# 8.net
KiCad netlist of a schematic drawn in EAGLE
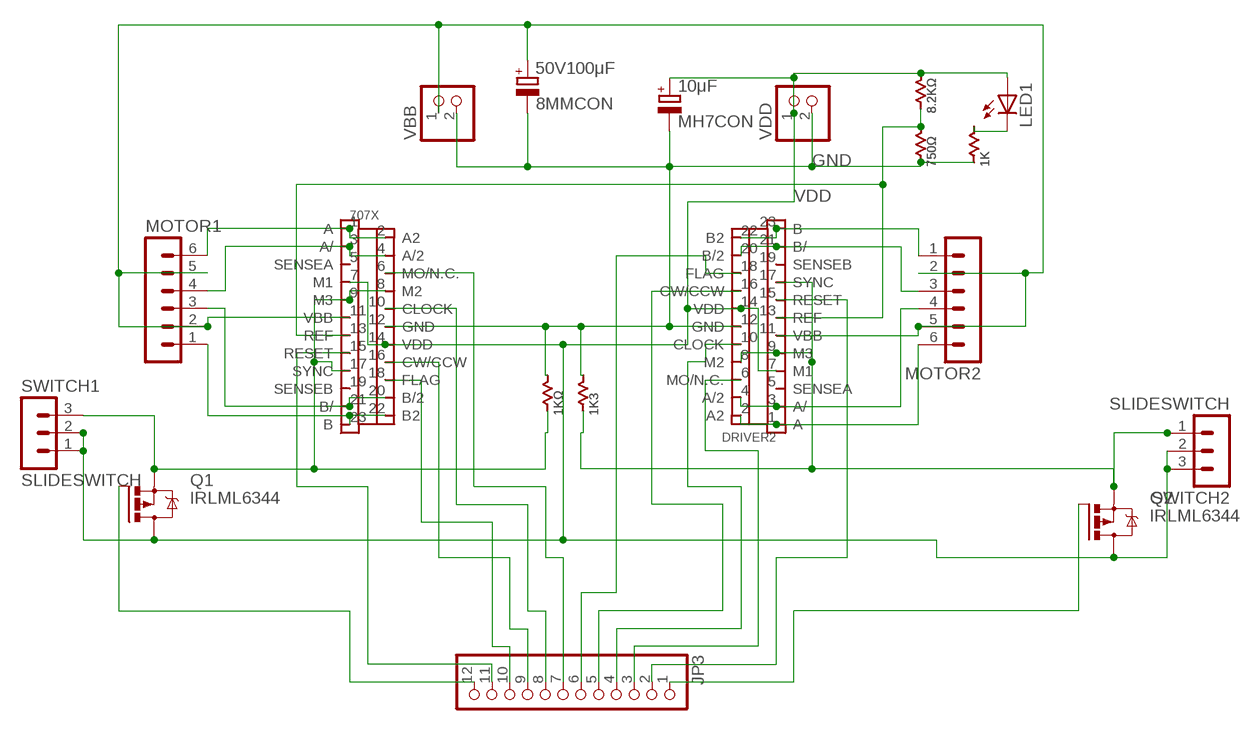
[diagram p0: schematic, sheet 1]

(export (version "E")
  (design (tool "Eeschema 10.0.6"))
  (components
    (comp (ref "1K")
      (value "R1608")
      (footprint "eagle-import:C1608")
      (libsource (lib "eagle-import") (part "R1608"))
    )
    (comp (ref "1K3")
      (value "R1608")
      (footprint "eagle-import:C1608")
      (libsource (lib "eagle-import") (part "R1608"))
    )
    (comp (ref "1KΩ")
      (value "R1608")
      (footprint "eagle-import:C1608")
      (libsource (lib "eagle-import") (part "R1608"))
    )
    (comp (ref "8.2KΩ")
      (value "1/6W")
      (footprint "eagle-import:1_6WRESISTANCE")
      (libsource (lib "eagle-import") (part "1/6W"))
    )
    (comp (ref "10μF")
      (value "MH7CON")
      (footprint "eagle-import:MH7CON")
      (libsource (lib "eagle-import") (part "MH7CON"))
    )
    (comp (ref "50V100μF")
      (value "8MMCON")
      (footprint "eagle-import:50V100FCON")
      (libsource (lib "eagle-import") (part "8MMCON"))
    )
    (comp (ref "707X")
      (value "SLA707X")
      (footprint "eagle-import:23-2PINHEAD")
      (libsource (lib "eagle-import") (part "SLA707X"))
    )
    (comp (ref "750Ω")
      (value "1/6W")
      (footprint "eagle-import:1_6WRESISTANCE")
      (libsource (lib "eagle-import") (part "1/6W"))
    )
    (comp (ref "DRIVER2")
      (value "SLA707X")
      (footprint "eagle-import:23-2PINHEAD")
      (libsource (lib "eagle-import") (part "SLA707X"))
    )
    (comp (ref "JP3")
      (value "PINHD-1X12")
      (footprint "eagle-import:1X12")
      (libsource (lib "eagle-import") (part "PINHD-1X12"))
    )
    (comp (ref "LED1")
      (value "OPTOCHIPLEDLED")
      (footprint "eagle-import:CHIP")
      (libsource (lib "eagle-import") (part "OPTOCHIPLEDLED"))
    )
    (comp (ref "MOTOR1")
      (value "MA06-1")
      (footprint "eagle-import:MA06-1")
      (libsource (lib "eagle-import") (part "MA06-1"))
    )
    (comp (ref "MOTOR2")
      (value "MA06-1")
      (footprint "eagle-import:MA06-1")
      (libsource (lib "eagle-import") (part "MA06-1"))
    )
    (comp (ref "Q1")
      (value "IRLML6344")
      (footprint "eagle-import:MICRO3")
      (libsource (lib "eagle-import") (part "IRLML5203"))
    )
    (comp (ref "Q2")
      (value "IRLML6344")
      (footprint "eagle-import:MICRO3")
      (libsource (lib "eagle-import") (part "IRLML5203"))
    )
    (comp (ref "SWITCH1")
      (value "SLIDESWITCH")
      (footprint "eagle-import:M251")
      (libsource (lib "eagle-import") (part "SLIDESWITCH"))
    )
    (comp (ref "SWITCH2")
      (value "SLIDESWITCH")
      (footprint "eagle-import:M251")
      (libsource (lib "eagle-import") (part "SLIDESWITCH"))
    )
    (comp (ref "VBB")
      (value "PINHD-1X2")
      (footprint "eagle-import:1X02")
      (libsource (lib "eagle-import") (part "PINHD-1X2"))
    )
    (comp (ref "VDD")
      (value "PINHD-1X2")
      (footprint "eagle-import:1X02")
      (libsource (lib "eagle-import") (part "PINHD-1X2"))
    )
  )
  (nets
    (net (code "1") (name "/GND") (class "Default")
      (node (ref "10μF") (pin "P$2") (pinfunction "-_P$2") (pintype "passive"))
      (node (ref "1K") (pin "2") (pinfunction "A_2") (pintype "bidirectional"))
      (node (ref "1K3") (pin "1") (pinfunction "B_1") (pintype "bidirectional"))
      (node (ref "1KΩ") (pin "1") (pinfunction "B_1") (pintype "bidirectional"))
      (node (ref "50V100μF") (pin "P$2") (pinfunction "-_P$2") (pintype "passive"))
      (node (ref "707X") (pin "12") (pinfunction "GND_12") (pintype "bidirectional"))
      (node (ref "750Ω") (pin "P$2") (pinfunction "A_P$2") (pintype "bidirectional"))
      (node (ref "DRIVER2") (pin "12") (pinfunction "GND_12") (pintype "bidirectional"))
      (node (ref "VBB") (pin "2") (pinfunction "2_2") (pintype "passive"))
      (node (ref "VDD") (pin "2") (pinfunction "2_2") (pintype "passive"))
    )
    (net (code "2") (name "/VDD") (class "Default")
      (node (ref "10μF") (pin "P$1") (pinfunction "+_P$1") (pintype "passive"))
      (node (ref "707X") (pin "14") (pinfunction "VDD_14") (pintype "bidirectional"))
      (node (ref "707X") (pin "7") (pinfunction "M1_7") (pintype "bidirectional"))
      (node (ref "8.2KΩ") (pin "P$1") (pinfunction "B_P$1") (pintype "bidirectional"))
      (node (ref "DRIVER2") (pin "14") (pinfunction "VDD_14") (pintype "bidirectional"))
      (node (ref "DRIVER2") (pin "7") (pinfunction "M1_7") (pintype "bidirectional"))
      (node (ref "LED1") (pin "P$1") (pinfunction "A_P$1") (pintype "passive"))
      (node (ref "Q1") (pin "3") (pinfunction "D_3") (pintype "passive"))
      (node (ref "Q2") (pin "3") (pinfunction "D_3") (pintype "passive"))
      (node (ref "SWITCH1") (pin "1") (pinfunction "1_1") (pintype "passive"))
      (node (ref "SWITCH1") (pin "2") (pinfunction "2_2") (pintype "passive"))
      (node (ref "SWITCH2") (pin "2") (pinfunction "2_2") (pintype "passive"))
      (node (ref "SWITCH2") (pin "3") (pinfunction "3_3") (pintype "passive"))
      (node (ref "VDD") (pin "1") (pinfunction "1_1") (pintype "passive"))
    )
    (net (code "3") (name "Net-(1K-B)") (class "Default")
      (node (ref "1K") (pin "1") (pinfunction "B_1") (pintype "bidirectional"))
      (node (ref "LED1") (pin "P$2") (pinfunction "C_P$2") (pintype "passive"))
    )
    (net (code "4") (name "Net-(1K3-A)") (class "Default")
      (node (ref "1K3") (pin "2") (pinfunction "A_2") (pintype "bidirectional"))
      (node (ref "DRIVER2") (pin "17") (pinfunction "SYNC_17") (pintype "bidirectional"))
      (node (ref "DRIVER2") (pin "8") (pinfunction "M2_8") (pintype "bidirectional"))
      (node (ref "DRIVER2") (pin "9") (pinfunction "M3_9") (pintype "bidirectional"))
      (node (ref "Q2") (pin "2") (pinfunction "S_2") (pintype "passive"))
      (node (ref "SWITCH2") (pin "1") (pinfunction "1_1") (pintype "passive"))
    )
    (net (code "5") (name "Net-(1KΩ-A)") (class "Default")
      (node (ref "1KΩ") (pin "2") (pinfunction "A_2") (pintype "bidirectional"))
      (node (ref "707X") (pin "17") (pinfunction "SYNC_17") (pintype "bidirectional"))
      (node (ref "707X") (pin "8") (pinfunction "M2_8") (pintype "bidirectional"))
      (node (ref "707X") (pin "9") (pinfunction "M3_9") (pintype "bidirectional"))
      (node (ref "Q1") (pin "2") (pinfunction "S_2") (pintype "passive"))
      (node (ref "SWITCH1") (pin "3") (pinfunction "3_3") (pintype "passive"))
    )
    (net (code "6") (name "Net-(50V100μF-+)") (class "Default")
      (node (ref "50V100μF") (pin "P$1") (pinfunction "+_P$1") (pintype "passive"))
      (node (ref "707X") (pin "11") (pinfunction "VBB_11") (pintype "bidirectional"))
      (node (ref "DRIVER2") (pin "11") (pinfunction "VBB_11") (pintype "bidirectional"))
      (node (ref "MOTOR1") (pin "2") (pinfunction "2_2") (pintype "passive"))
      (node (ref "MOTOR1") (pin "5") (pinfunction "5_5") (pintype "passive"))
      (node (ref "MOTOR2") (pin "2") (pinfunction "2_2") (pintype "passive"))
      (node (ref "MOTOR2") (pin "5") (pinfunction "5_5") (pintype "passive"))
      (node (ref "VBB") (pin "1") (pinfunction "1_1") (pintype "passive"))
    )
    (net (code "7") (name "Net-(707X-A)") (class "Default")
      (node (ref "707X") (pin "1") (pinfunction "A_1") (pintype "bidirectional"))
      (node (ref "707X") (pin "2") (pinfunction "A2_2") (pintype "bidirectional"))
      (node (ref "MOTOR1") (pin "6") (pinfunction "6_6") (pintype "passive"))
    )
    (net (code "8") (name "Net-(707X-A{slash})") (class "Default")
      (node (ref "707X") (pin "3") (pinfunction "A/_3") (pintype "bidirectional"))
      (node (ref "707X") (pin "4") (pinfunction "A/2_4") (pintype "bidirectional"))
      (node (ref "MOTOR1") (pin "4") (pinfunction "4_4") (pintype "passive"))
    )
    (net (code "9") (name "Net-(707X-B)") (class "Default")
      (node (ref "707X") (pin "22") (pinfunction "B2_22") (pintype "bidirectional"))
      (node (ref "707X") (pin "23") (pinfunction "B_23") (pintype "bidirectional"))
      (node (ref "MOTOR1") (pin "1") (pinfunction "1_1") (pintype "passive"))
    )
    (net (code "10") (name "Net-(707X-B{slash})") (class "Default")
      (node (ref "707X") (pin "20") (pinfunction "B/2_20") (pintype "bidirectional"))
      (node (ref "707X") (pin "21") (pinfunction "B/_21") (pintype "bidirectional"))
      (node (ref "MOTOR1") (pin "3") (pinfunction "3_3") (pintype "passive"))
    )
    (net (code "11") (name "Net-(707X-CLOCK)") (class "Default")
      (node (ref "707X") (pin "10") (pinfunction "CLOCK_10") (pintype "bidirectional"))
      (node (ref "JP3") (pin "8") (pinfunction "8_8") (pintype "passive"))
    )
    (net (code "12") (name "Net-(707X-CW{slash}CCW)") (class "Default")
      (node (ref "707X") (pin "16") (pinfunction "CW/CCW_16") (pintype "bidirectional"))
      (node (ref "JP3") (pin "9") (pinfunction "9_9") (pintype "passive"))
    )
    (net (code "13") (name "Net-(707X-FLAG)") (class "Default")
      (node (ref "707X") (pin "18") (pinfunction "FLAG_18") (pintype "bidirectional"))
      (node (ref "JP3") (pin "10") (pinfunction "10_10") (pintype "passive"))
    )
    (net (code "14") (name "Net-(707X-MO{slash}N.C.)") (class "Default")
      (node (ref "707X") (pin "6") (pinfunction "MO/N.C._6") (pintype "bidirectional"))
      (node (ref "JP3") (pin "7") (pinfunction "7_7") (pintype "passive"))
    )
    (net (code "15") (name "Net-(707X-REF)") (class "Default")
      (node (ref "707X") (pin "13") (pinfunction "REF_13") (pintype "bidirectional"))
      (node (ref "750Ω") (pin "P$1") (pinfunction "B_P$1") (pintype "bidirectional"))
      (node (ref "8.2KΩ") (pin "P$2") (pinfunction "A_P$2") (pintype "bidirectional"))
      (node (ref "DRIVER2") (pin "13") (pinfunction "REF_13") (pintype "bidirectional"))
    )
    (net (code "16") (name "Net-(707X-RESET)") (class "Default")
      (node (ref "707X") (pin "15") (pinfunction "RESET_15") (pintype "bidirectional"))
      (node (ref "JP3") (pin "11") (pinfunction "11_11") (pintype "passive"))
    )
    (net (code "17") (name "Net-(DRIVER2-A)") (class "Default")
      (node (ref "DRIVER2") (pin "1") (pinfunction "A_1") (pintype "bidirectional"))
      (node (ref "DRIVER2") (pin "2") (pinfunction "A2_2") (pintype "bidirectional"))
      (node (ref "MOTOR2") (pin "6") (pinfunction "6_6") (pintype "passive"))
    )
    (net (code "18") (name "Net-(DRIVER2-A{slash})") (class "Default")
      (node (ref "DRIVER2") (pin "3") (pinfunction "A/_3") (pintype "bidirectional"))
      (node (ref "DRIVER2") (pin "4") (pinfunction "A/2_4") (pintype "bidirectional"))
      (node (ref "MOTOR2") (pin "4") (pinfunction "4_4") (pintype "passive"))
    )
    (net (code "19") (name "Net-(DRIVER2-B)") (class "Default")
      (node (ref "DRIVER2") (pin "22") (pinfunction "B2_22") (pintype "bidirectional"))
      (node (ref "DRIVER2") (pin "23") (pinfunction "B_23") (pintype "bidirectional"))
      (node (ref "MOTOR2") (pin "1") (pinfunction "1_1") (pintype "passive"))
    )
    (net (code "20") (name "Net-(DRIVER2-B{slash})") (class "Default")
      (node (ref "DRIVER2") (pin "20") (pinfunction "B/2_20") (pintype "bidirectional"))
      (node (ref "DRIVER2") (pin "21") (pinfunction "B/_21") (pintype "bidirectional"))
      (node (ref "MOTOR2") (pin "3") (pinfunction "3_3") (pintype "passive"))
    )
    (net (code "21") (name "Net-(DRIVER2-CLOCK)") (class "Default")
      (node (ref "DRIVER2") (pin "10") (pinfunction "CLOCK_10") (pintype "bidirectional"))
      (node (ref "JP3") (pin "4") (pinfunction "4_4") (pintype "passive"))
    )
    (net (code "22") (name "Net-(DRIVER2-CW{slash}CCW)") (class "Default")
      (node (ref "DRIVER2") (pin "16") (pinfunction "CW/CCW_16") (pintype "bidirectional"))
      (node (ref "JP3") (pin "5") (pinfunction "5_5") (pintype "passive"))
    )
    (net (code "23") (name "Net-(DRIVER2-FLAG)") (class "Default")
      (node (ref "DRIVER2") (pin "18") (pinfunction "FLAG_18") (pintype "bidirectional"))
      (node (ref "JP3") (pin "6") (pinfunction "6_6") (pintype "passive"))
    )
    (net (code "24") (name "Net-(DRIVER2-MO{slash}N.C.)") (class "Default")
      (node (ref "DRIVER2") (pin "6") (pinfunction "MO/N.C._6") (pintype "bidirectional"))
      (node (ref "JP3") (pin "3") (pinfunction "3_3") (pintype "passive"))
    )
    (net (code "25") (name "Net-(DRIVER2-RESET)") (class "Default")
      (node (ref "DRIVER2") (pin "15") (pinfunction "RESET_15") (pintype "bidirectional"))
      (node (ref "JP3") (pin "2") (pinfunction "2_2") (pintype "passive"))
    )
    (net (code "26") (name "Net-(Q1-G)") (class "Default")
      (node (ref "JP3") (pin "12") (pinfunction "12_12") (pintype "passive"))
      (node (ref "Q1") (pin "1") (pinfunction "G_1") (pintype "passive"))
    )
    (net (code "27") (name "Net-(Q2-G)") (class "Default")
      (node (ref "JP3") (pin "1") (pinfunction "1_1") (pintype "passive"))
      (node (ref "Q2") (pin "1") (pinfunction "G_1") (pintype "passive"))
    )
    (net (code "28") (name "unconnected-(707X-SENSEA-Pad5)") (class "Default")
      (node (ref "707X") (pin "5") (pinfunction "SENSEA_5") (pintype "bidirectional"))
    )
    (net (code "29") (name "unconnected-(707X-SENSEB-Pad19)") (class "Default")
      (node (ref "707X") (pin "19") (pinfunction "SENSEB_19") (pintype "bidirectional"))
    )
    (net (code "30") (name "unconnected-(DRIVER2-SENSEA-Pad5)") (class "Default")
      (node (ref "DRIVER2") (pin "5") (pinfunction "SENSEA_5") (pintype "bidirectional"))
    )
    (net (code "31") (name "unconnected-(DRIVER2-SENSEB-Pad19)") (class "Default")
      (node (ref "DRIVER2") (pin "19") (pinfunction "SENSEB_19") (pintype "bidirectional"))
    )
  )
)
